# E17-15-Buttons.net
KiCad netlist of a schematic drawn in Altium Designer
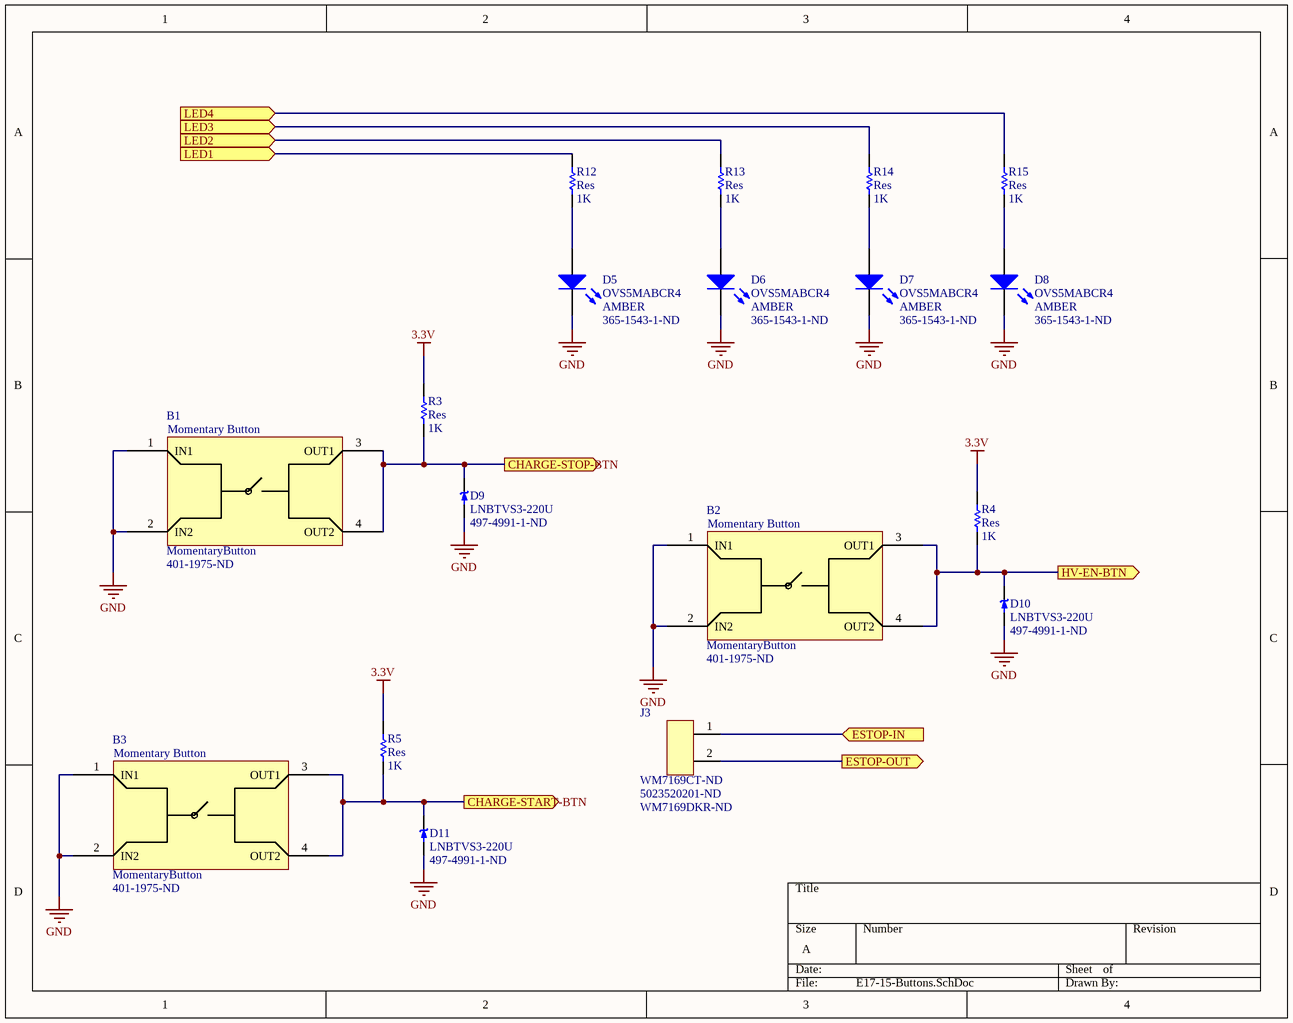
[diagram p0: E17-15-Buttons.SchDoc]

(export (version "E")
  (design (tool "Eeschema 10.0.6"))
  (components
    (comp (ref "B1")
      (value "MomentaryButton")
      (footprint "MomentaryButton")
      (fields (field (name "DIGIKEY PART NUMBER") "401-1975-ND"))
      (libsource (lib "MomentaryButton") (part "MomentaryButton"))
    )
    (comp (ref "B2")
      (value "MomentaryButton")
      (footprint "MomentaryButton")
      (fields (field (name "DIGIKEY PART NUMBER") "401-1975-ND"))
      (libsource (lib "MomentaryButton") (part "MomentaryButton"))
    )
    (comp (ref "B3")
      (value "MomentaryButton")
      (footprint "MomentaryButton")
      (fields (field (name "DIGIKEY PART NUMBER") "401-1975-ND"))
      (libsource (lib "MomentaryButton") (part "MomentaryButton"))
    )
    (comp (ref "D5")
      (value "OVS5MABCR4")
      (footprint "OVS5MABCR4")
      (description "Typical AMBER LED")
      (fields
        (field (name "COLOUR") "AMBER")
        (field (name "SUPPLIER PART NUMBER 1") "365-1543-1-ND")
        (field (name "PUBLISHER") "Altium Limited")
      )
      (libsource (lib "LEDs") (part "OVS5MABCR4"))
    )
    (comp (ref "D6")
      (value "OVS5MABCR4")
      (footprint "OVS5MABCR4")
      (description "Typical AMBER LED")
      (fields
        (field (name "COLOUR") "AMBER")
        (field (name "SUPPLIER PART NUMBER 1") "365-1543-1-ND")
        (field (name "PUBLISHER") "Altium Limited")
      )
      (libsource (lib "LEDs") (part "OVS5MABCR4"))
    )
    (comp (ref "D7")
      (value "OVS5MABCR4")
      (footprint "OVS5MABCR4")
      (description "Typical AMBER LED")
      (fields
        (field (name "COLOUR") "AMBER")
        (field (name "SUPPLIER PART NUMBER 1") "365-1543-1-ND")
        (field (name "PUBLISHER") "Altium Limited")
      )
      (libsource (lib "LEDs") (part "OVS5MABCR4"))
    )
    (comp (ref "D8")
      (value "OVS5MABCR4")
      (footprint "OVS5MABCR4")
      (description "Typical AMBER LED")
      (fields
        (field (name "COLOUR") "AMBER")
        (field (name "SUPPLIER PART NUMBER 1") "365-1543-1-ND")
        (field (name "PUBLISHER") "Altium Limited")
      )
      (libsource (lib "LEDs") (part "OVS5MABCR4"))
    )
    (comp (ref "D9")
      (value "LNBTVS3-220U")
      (footprint "DO-214-AA")
      (description "TVS DIODE 20VWM 35VC SMB")
      (fields (field (name "SUPPLIER PART NUMBER 1") "497-4991-1-ND"))
      (libsource (lib "Diodes") (part "LNBTVS3-220U"))
    )
    (comp (ref "D10")
      (value "LNBTVS3-220U")
      (footprint "DO-214-AA")
      (description "TVS DIODE 20VWM 35VC SMB")
      (fields (field (name "SUPPLIER PART NUMBER 1") "497-4991-1-ND"))
      (libsource (lib "Diodes") (part "LNBTVS3-220U"))
    )
    (comp (ref "D11")
      (value "LNBTVS3-220U")
      (footprint "DO-214-AA")
      (description "TVS DIODE 20VWM 35VC SMB")
      (fields (field (name "SUPPLIER PART NUMBER 1") "497-4991-1-ND"))
      (libsource (lib "Diodes") (part "LNBTVS3-220U"))
    )
    (comp (ref "J3")
      (value "J_5023520200")
      (footprint "MOLEX_DURACLIK_2")
      (description "MOLEX DURACLIK 2-PIN RA")
      (fields
        (field (name "SUPPLIER PART NUMBER 1") "5023520201-ND")
        (field (name "SUPPLIER PART NUMBER 2") "WM7169DKR-ND")
      )
      (libsource (lib "Molex_DuraClik") (part "J_5023520200"))
    )
    (comp (ref "R3")
      (value "Res")
      (footprint "2012[0805]")
      (description "Surface Mount Resistor")
      (fields (field (name "ALTIUM_VALUE") "1K") (field (name "PUBLISHER") "Altium Limited"))
      (libsource (lib "Resistors") (part "Res"))
    )
    (comp (ref "R4")
      (value "Res")
      (footprint "2012[0805]")
      (description "Surface Mount Resistor")
      (fields (field (name "ALTIUM_VALUE") "1K") (field (name "PUBLISHER") "Altium Limited"))
      (libsource (lib "Resistors") (part "Res"))
    )
    (comp (ref "R5")
      (value "Res")
      (footprint "2012[0805]")
      (description "Surface Mount Resistor")
      (fields (field (name "ALTIUM_VALUE") "1K") (field (name "PUBLISHER") "Altium Limited"))
      (libsource (lib "Resistors") (part "Res"))
    )
    (comp (ref "R12")
      (value "Res")
      (footprint "3216[1206]")
      (description "Surface Mount Resistor")
      (fields (field (name "ALTIUM_VALUE") "1K") (field (name "PUBLISHER") "Altium Limited"))
      (libsource (lib "Resistors") (part "Res"))
    )
    (comp (ref "R13")
      (value "Res")
      (footprint "3216[1206]")
      (description "Surface Mount Resistor")
      (fields (field (name "ALTIUM_VALUE") "1K") (field (name "PUBLISHER") "Altium Limited"))
      (libsource (lib "Resistors") (part "Res"))
    )
    (comp (ref "R14")
      (value "Res")
      (footprint "3216[1206]")
      (description "Surface Mount Resistor")
      (fields (field (name "ALTIUM_VALUE") "1K") (field (name "PUBLISHER") "Altium Limited"))
      (libsource (lib "Resistors") (part "Res"))
    )
    (comp (ref "R15")
      (value "Res")
      (footprint "3216[1206]")
      (description "Surface Mount Resistor")
      (fields (field (name "ALTIUM_VALUE") "1K") (field (name "PUBLISHER") "Altium Limited"))
      (libsource (lib "Resistors") (part "Res"))
    )
  )
  (nets
    (net (code "1") (name "/CHARGE-START-BTN") (class "Default")
      (node (ref "B3") (pin "3") (pinfunction "OUT1_3") (pintype "passive"))
      (node (ref "B3") (pin "4") (pinfunction "OUT2_4") (pintype "passive"))
      (node (ref "D11") (pin "2") (pinfunction "2_2") (pintype "passive"))
      (node (ref "R5") (pin "1") (pinfunction "1_1") (pintype "passive"))
    )
    (net (code "2") (name "/CHARGE-STOP-BTN") (class "Default")
      (node (ref "B1") (pin "3") (pinfunction "OUT1_3") (pintype "passive"))
      (node (ref "B1") (pin "4") (pinfunction "OUT2_4") (pintype "passive"))
      (node (ref "D9") (pin "2") (pinfunction "2_2") (pintype "passive"))
      (node (ref "R3") (pin "1") (pinfunction "1_1") (pintype "passive"))
    )
    (net (code "3") (name "/ESTOP-IN") (class "Default")
      (node (ref "J3") (pin "1") (pinfunction "1_1") (pintype "passive"))
    )
    (net (code "4") (name "/ESTOP-OUT") (class "Default")
      (node (ref "J3") (pin "2") (pinfunction "2_2") (pintype "passive"))
    )
    (net (code "5") (name "/HV-EN-BTN") (class "Default")
      (node (ref "B2") (pin "3") (pinfunction "OUT1_3") (pintype "passive"))
      (node (ref "B2") (pin "4") (pinfunction "OUT2_4") (pintype "passive"))
      (node (ref "D10") (pin "2") (pinfunction "2_2") (pintype "passive"))
      (node (ref "R4") (pin "1") (pinfunction "1_1") (pintype "passive"))
    )
    (net (code "6") (name "/LED1") (class "Default")
      (node (ref "R12") (pin "1") (pinfunction "1_1") (pintype "passive"))
    )
    (net (code "7") (name "/LED2") (class "Default")
      (node (ref "R13") (pin "1") (pinfunction "1_1") (pintype "passive"))
    )
    (net (code "8") (name "/LED3") (class "Default")
      (node (ref "R14") (pin "1") (pinfunction "1_1") (pintype "passive"))
    )
    (net (code "9") (name "/LED4") (class "Default")
      (node (ref "R15") (pin "1") (pinfunction "1_1") (pintype "passive"))
    )
    (net (code "10") (name "3.3V") (class "Default")
      (node (ref "R3") (pin "2") (pinfunction "2_2") (pintype "passive"))
      (node (ref "R4") (pin "2") (pinfunction "2_2") (pintype "passive"))
      (node (ref "R5") (pin "2") (pinfunction "2_2") (pintype "passive"))
    )
    (net (code "11") (name "GND") (class "Default")
      (node (ref "B1") (pin "1") (pinfunction "IN1_1") (pintype "passive"))
      (node (ref "B1") (pin "2") (pinfunction "IN2_2") (pintype "passive"))
      (node (ref "B2") (pin "1") (pinfunction "IN1_1") (pintype "passive"))
      (node (ref "B2") (pin "2") (pinfunction "IN2_2") (pintype "passive"))
      (node (ref "B3") (pin "1") (pinfunction "IN1_1") (pintype "passive"))
      (node (ref "B3") (pin "2") (pinfunction "IN2_2") (pintype "passive"))
      (node (ref "D10") (pin "1") (pinfunction "1_1") (pintype "passive"))
      (node (ref "D11") (pin "1") (pinfunction "1_1") (pintype "passive"))
      (node (ref "D5") (pin "2") (pinfunction "K_2") (pintype "passive"))
      (node (ref "D6") (pin "2") (pinfunction "K_2") (pintype "passive"))
      (node (ref "D7") (pin "2") (pinfunction "K_2") (pintype "passive"))
      (node (ref "D8") (pin "2") (pinfunction "K_2") (pintype "passive"))
      (node (ref "D9") (pin "1") (pinfunction "1_1") (pintype "passive"))
    )
    (net (code "12") (name "Net-(D5-A)") (class "Default")
      (node (ref "D5") (pin "1") (pinfunction "A_1") (pintype "passive"))
      (node (ref "R12") (pin "2") (pinfunction "2_2") (pintype "passive"))
    )
    (net (code "13") (name "Net-(D6-A)") (class "Default")
      (node (ref "D6") (pin "1") (pinfunction "A_1") (pintype "passive"))
      (node (ref "R13") (pin "2") (pinfunction "2_2") (pintype "passive"))
    )
    (net (code "14") (name "Net-(D7-A)") (class "Default")
      (node (ref "D7") (pin "1") (pinfunction "A_1") (pintype "passive"))
      (node (ref "R14") (pin "2") (pinfunction "2_2") (pintype "passive"))
    )
    (net (code "15") (name "Net-(D8-A)") (class "Default")
      (node (ref "D8") (pin "1") (pinfunction "A_1") (pintype "passive"))
      (node (ref "R15") (pin "2") (pinfunction "2_2") (pintype "passive"))
    )
  )
)
